# Logic_Analyzer.net
KiCad netlist of a schematic drawn in Altium Designer
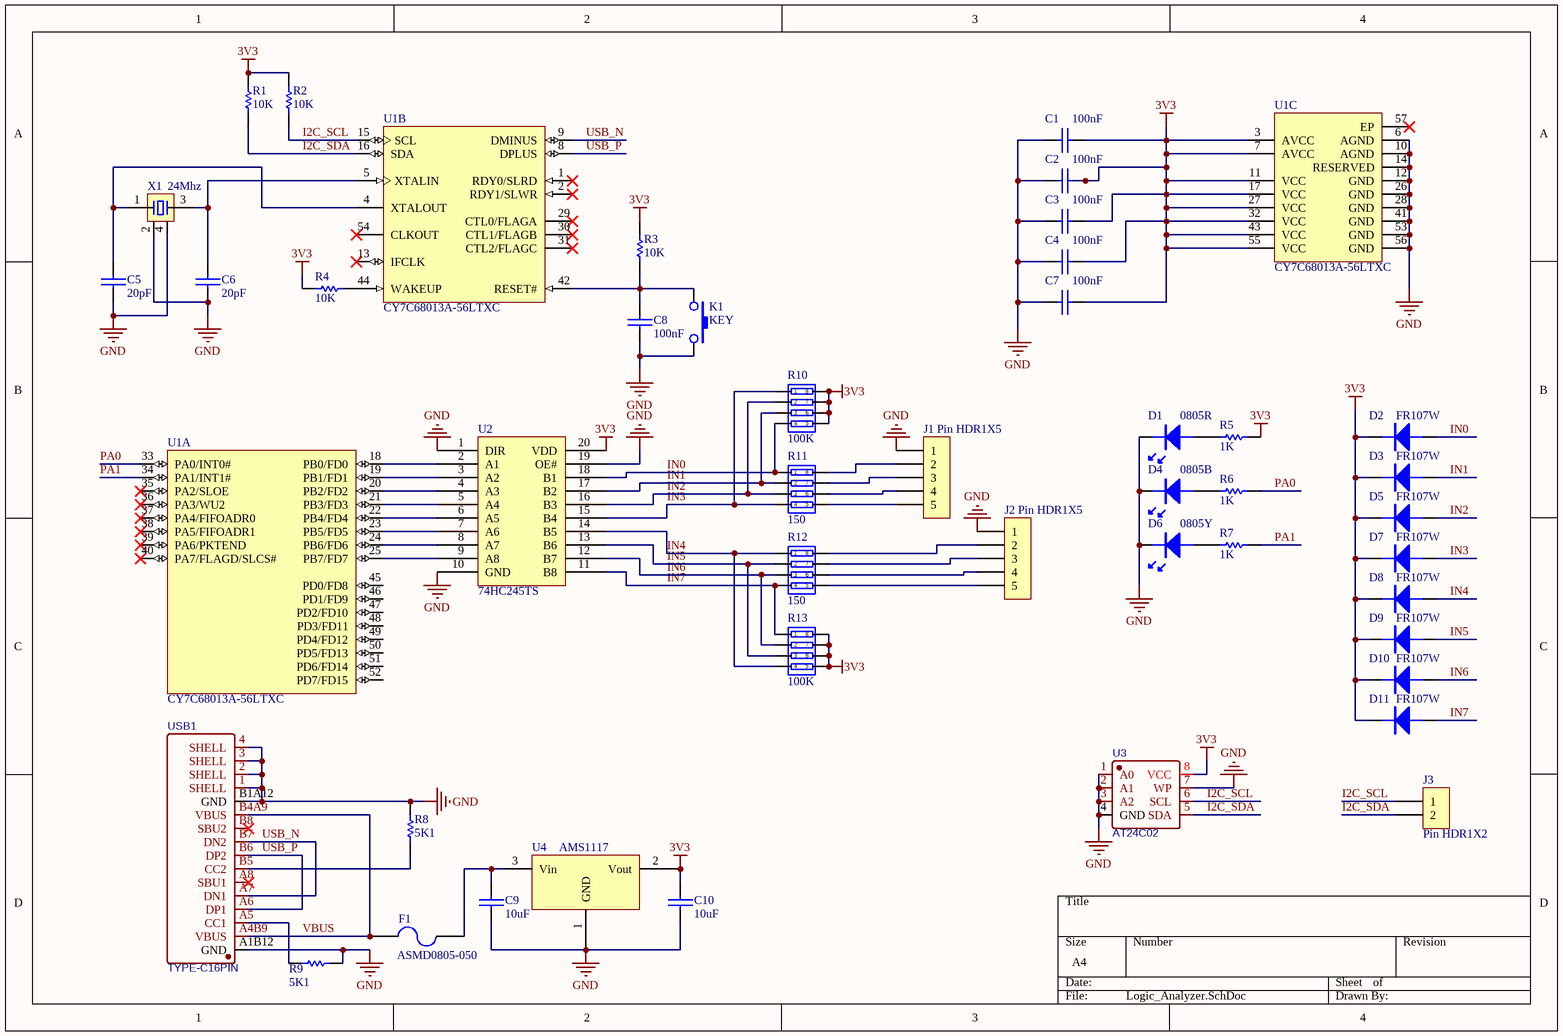
[diagram p0: Logic_Analyzer.SchDoc]

(export (version "E")
  (design (tool "Eeschema 10.0.6"))
  (components
    (comp (ref "C1")
      (value "100nF")
      (footprint "0603C")
      (description "无极性电容")
      (libsource (lib "电容") (part "CAP"))
    )
    (comp (ref "C2")
      (value "100nF")
      (footprint "0603C")
      (description "无极性电容")
      (libsource (lib "电容") (part "CAP"))
    )
    (comp (ref "C3")
      (value "100nF")
      (footprint "0603C")
      (description "无极性电容")
      (libsource (lib "电容") (part "CAP"))
    )
    (comp (ref "C4")
      (value "100nF")
      (footprint "0603C")
      (description "无极性电容")
      (libsource (lib "电容") (part "CAP"))
    )
    (comp (ref "C5")
      (value "20pF")
      (footprint "0603C")
      (description "无极性电容")
      (libsource (lib "电容") (part "CAP"))
    )
    (comp (ref "C6")
      (value "20pF")
      (footprint "0603C")
      (description "无极性电容")
      (libsource (lib "电容") (part "CAP"))
    )
    (comp (ref "C7")
      (value "100nF")
      (footprint "0603C")
      (description "无极性电容")
      (libsource (lib "电容") (part "CAP"))
    )
    (comp (ref "C8")
      (value "100nF")
      (footprint "0603C")
      (description "无极性电容")
      (libsource (lib "电容") (part "CAP"))
    )
    (comp (ref "C9")
      (value "10uF")
      (footprint "0603C")
      (description "无极性电容")
      (libsource (lib "电容") (part "CAP"))
    )
    (comp (ref "C10")
      (value "10uF")
      (footprint "0603C")
      (description "无极性电容")
      (libsource (lib "电容") (part "CAP"))
    )
    (comp (ref "D1") (value "0805R") (footprint "LED-0805R") (libsource (lib "LED") (part "LED")))
    (comp (ref "D2")
      (value "FR107W")
      (footprint "SOD-123")
      (description "普通二极管")
      (libsource (lib "二极管") (part "DIODE"))
    )
    (comp (ref "D3")
      (value "FR107W")
      (footprint "SOD-123")
      (description "普通二极管")
      (libsource (lib "二极管") (part "DIODE"))
    )
    (comp (ref "D4") (value "0805B") (footprint "LED-0805B") (libsource (lib "LED") (part "LED")))
    (comp (ref "D5")
      (value "FR107W")
      (footprint "SOD-123")
      (description "普通二极管")
      (libsource (lib "二极管") (part "DIODE"))
    )
    (comp (ref "D6") (value "0805Y") (footprint "LED-0805Y") (libsource (lib "LED") (part "LED")))
    (comp (ref "D7")
      (value "FR107W")
      (footprint "SOD-123")
      (description "普通二极管")
      (libsource (lib "二极管") (part "DIODE"))
    )
    (comp (ref "D8")
      (value "FR107W")
      (footprint "SOD-123")
      (description "普通二极管")
      (libsource (lib "二极管") (part "DIODE"))
    )
    (comp (ref "D9")
      (value "FR107W")
      (footprint "SOD-123")
      (description "普通二极管")
      (libsource (lib "二极管") (part "DIODE"))
    )
    (comp (ref "D10")
      (value "FR107W")
      (footprint "SOD-123")
      (description "普通二极管")
      (libsource (lib "二极管") (part "DIODE"))
    )
    (comp (ref "D11")
      (value "FR107W")
      (footprint "SOD-123")
      (description "普通二极管")
      (libsource (lib "二极管") (part "DIODE"))
    )
    (comp (ref "F1") (value "ASMD0805-050") (footprint "FUSE-0805") (libsource (lib "保险丝") (part "FUSE")))
    (comp (ref "J1")
      (value "Pin HDR1X5")
      (footprint "Pin HDR1X5/2.54mm-S-SMD")
      (libsource (lib "排针") (part "Pin HDR1X5"))
    )
    (comp (ref "J2")
      (value "Pin HDR1X5")
      (footprint "Pin HDR1X5/2.54mm-S-SMD")
      (libsource (lib "排针") (part "Pin HDR1X5"))
    )
    (comp (ref "J3")
      (value "Pin HDR1X2")
      (footprint "Pin HDR1X2/2.54mm-S")
      (libsource (lib "排针") (part "Pin HDR1X2"))
    )
    (comp (ref "K1")
      (value "KEY")
      (footprint "SW-SMD_L4.0-W2.9-P4.15-EH")
      (libsource (lib "轻触开关") (part "KEY"))
    )
    (comp (ref "R1") (value "10K") (footprint "0603R") (libsource (lib "电阻") (part "RES")))
    (comp (ref "R2") (value "10K") (footprint "0603R") (libsource (lib "电阻") (part "RES")))
    (comp (ref "R3") (value "10K") (footprint "0603R") (libsource (lib "电阻") (part "RES")))
    (comp (ref "R4") (value "10K") (footprint "0603R") (libsource (lib "电阻") (part "RES")))
    (comp (ref "R5") (value "1K") (footprint "0603R") (libsource (lib "电阻") (part "RES")))
    (comp (ref "R6") (value "1K") (footprint "0603R") (libsource (lib "电阻") (part "RES")))
    (comp (ref "R7") (value "1K") (footprint "0603R") (libsource (lib "电阻") (part "RES")))
    (comp (ref "R8") (value "5K1") (footprint "0603R") (libsource (lib "电阻") (part "RES")))
    (comp (ref "R9") (value "5K1") (footprint "0603R") (libsource (lib "电阻") (part "RES")))
    (comp (ref "R10")
      (value "100K")
      (footprint "RES-ARRAY-SMD_0603-8P-L3.2-W1.6-BL")
      (description "网络排阻4R")
      (libsource (lib "电阻") (part "RES_ARRAY*4"))
    )
    (comp (ref "R11")
      (value "150")
      (footprint "RES-ARRAY-SMD_0603-8P-L3.2-W1.6-BL")
      (description "网络排阻4R")
      (libsource (lib "电阻") (part "RES_ARRAY*4"))
    )
    (comp (ref "R12")
      (value "150")
      (footprint "RES-ARRAY-SMD_0603-8P-L3.2-W1.6-BL")
      (description "网络排阻4R")
      (libsource (lib "电阻") (part "RES_ARRAY*4"))
    )
    (comp (ref "R13")
      (value "100K")
      (footprint "RES-ARRAY-SMD_0603-8P-L3.2-W1.6-BL")
      (description "网络排阻4R")
      (libsource (lib "电阻") (part "RES_ARRAY*4"))
    )
    (comp (ref "U1")
      (value "CY7C68013A-56LTXC")
      (footprint "CYP-LTX56-5200X4500TP_M")
      (fields (field (name "MANUFACTURER") "Cypress"))
      (libsource (lib "Cypress USB Controllers") (part "CY7C68013A-56LTXC"))
    )
    (comp (ref "U2") (value "74HC245TS") (footprint "TSSOP20") (libsource (lib "74系列芯片") (part "74HC245TS")))
    (comp (ref "U3")
      (value "AT24C02")
      (footprint "SOP8")
      (fields (field (name "BOM_SUPPLIER PART") "C688857") (field (name "CONTRIBUTOR") "LCSC"))
      (libsource (lib "未分类IC") (part "AT24C02"))
    )
    (comp (ref "U4")
      (value "AMS1117")
      (footprint "SOT223")
      (description "三端稳压芯片")
      (libsource (lib "电源芯片") (part "AMS1117"))
    )
    (comp (ref "USB1")
      (value "TYPE-C16PIN")
      (footprint "USB-C-SMD_TYPE-C16PIN")
      (fields (field (name "BOM_SUPPLIER PART") "C393939") (field (name "CONTRIBUTOR") "LCSC"))
      (libsource (lib "USB") (part "USB-C_16PIN"))
    )
    (comp (ref "X1")
      (value "24Mhz")
      (footprint "OSC 3225-4P")
      (description "4脚无源晶振")
      (libsource (lib "晶振") (part "XTAL-4P"))
    )
  )
  (nets
    (net (code "1") (name "/I2C_SCL") (class "Default")
      (node (ref "J3") (pin "1") (pinfunction "1_1") (pintype "passive"))
      (node (ref "R2") (pin "1") (pinfunction "1_1") (pintype "passive"))
      (node (ref "U1") (pin "15") (pinfunction "SCL_15") (pintype "bidirectional"))
      (node (ref "U3") (pin "6") (pinfunction "SCL_6") (pintype "passive"))
    )
    (net (code "2") (name "/I2C_SDA") (class "Default")
      (node (ref "J3") (pin "2") (pinfunction "2_2") (pintype "passive"))
      (node (ref "R1") (pin "1") (pinfunction "1_1") (pintype "passive"))
      (node (ref "U1") (pin "16") (pinfunction "SDA_16") (pintype "bidirectional"))
      (node (ref "U3") (pin "5") (pinfunction "SDA_5") (pintype "passive"))
    )
    (net (code "3") (name "/IN0") (class "Default")
      (node (ref "D2") (pin "A") (pinfunction "A_A") (pintype "passive"))
      (node (ref "R10") (pin "4") (pinfunction "4_4") (pintype "passive"))
      (node (ref "R11") (pin "1") (pinfunction "1_1") (pintype "passive"))
      (node (ref "U2") (pin "18") (pinfunction "B1_18") (pintype "passive"))
    )
    (net (code "4") (name "/IN1") (class "Default")
      (node (ref "D3") (pin "A") (pinfunction "A_A") (pintype "passive"))
      (node (ref "R10") (pin "3") (pinfunction "3_3") (pintype "passive"))
      (node (ref "R11") (pin "2") (pinfunction "2_2") (pintype "passive"))
      (node (ref "U2") (pin "17") (pinfunction "B2_17") (pintype "passive"))
    )
    (net (code "5") (name "/IN2") (class "Default")
      (node (ref "D5") (pin "A") (pinfunction "A_A") (pintype "passive"))
      (node (ref "R10") (pin "2") (pinfunction "2_2") (pintype "passive"))
      (node (ref "R11") (pin "3") (pinfunction "3_3") (pintype "passive"))
      (node (ref "U2") (pin "16") (pinfunction "B3_16") (pintype "passive"))
    )
    (net (code "6") (name "/IN3") (class "Default")
      (node (ref "D7") (pin "A") (pinfunction "A_A") (pintype "passive"))
      (node (ref "R10") (pin "1") (pinfunction "1_1") (pintype "passive"))
      (node (ref "R11") (pin "4") (pinfunction "4_4") (pintype "passive"))
      (node (ref "U2") (pin "15") (pinfunction "B4_15") (pintype "passive"))
    )
    (net (code "7") (name "/IN4") (class "Default")
      (node (ref "D8") (pin "A") (pinfunction "A_A") (pintype "passive"))
      (node (ref "R12") (pin "1") (pinfunction "1_1") (pintype "passive"))
      (node (ref "R13") (pin "4") (pinfunction "4_4") (pintype "passive"))
      (node (ref "U2") (pin "14") (pinfunction "B5_14") (pintype "passive"))
    )
    (net (code "8") (name "/IN5") (class "Default")
      (node (ref "D9") (pin "A") (pinfunction "A_A") (pintype "passive"))
      (node (ref "R12") (pin "2") (pinfunction "2_2") (pintype "passive"))
      (node (ref "R13") (pin "3") (pinfunction "3_3") (pintype "passive"))
      (node (ref "U2") (pin "13") (pinfunction "B6_13") (pintype "passive"))
    )
    (net (code "9") (name "/IN6") (class "Default")
      (node (ref "D10") (pin "A") (pinfunction "A_A") (pintype "passive"))
      (node (ref "R12") (pin "3") (pinfunction "3_3") (pintype "passive"))
      (node (ref "R13") (pin "2") (pinfunction "2_2") (pintype "passive"))
      (node (ref "U2") (pin "12") (pinfunction "B7_12") (pintype "passive"))
    )
    (net (code "10") (name "/IN7") (class "Default")
      (node (ref "D11") (pin "A") (pinfunction "A_A") (pintype "passive"))
      (node (ref "R12") (pin "4") (pinfunction "4_4") (pintype "passive"))
      (node (ref "R13") (pin "1") (pinfunction "1_1") (pintype "passive"))
      (node (ref "U2") (pin "11") (pinfunction "B8_11") (pintype "passive"))
    )
    (net (code "11") (name "/PA0") (class "Default")
      (node (ref "R6") (pin "1") (pinfunction "1_1") (pintype "passive"))
      (node (ref "U1") (pin "33") (pinfunction "PA0/INT0#_33") (pintype "bidirectional"))
    )
    (net (code "12") (name "/PA1") (class "Default")
      (node (ref "R7") (pin "1") (pinfunction "1_1") (pintype "passive"))
      (node (ref "U1") (pin "34") (pinfunction "PA1/INT1#_34") (pintype "bidirectional"))
    )
    (net (code "13") (name "/USB_N") (class "Default")
      (node (ref "U1") (pin "9") (pinfunction "DMINUS_9") (pintype "bidirectional"))
      (node (ref "USB1") (pin "A7") (pinfunction "DN1_A7") (pintype "passive"))
      (node (ref "USB1") (pin "B7") (pinfunction "DN2_B7") (pintype "passive"))
    )
    (net (code "14") (name "/USB_P") (class "Default")
      (node (ref "U1") (pin "8") (pinfunction "DPLUS_8") (pintype "bidirectional"))
      (node (ref "USB1") (pin "A6") (pinfunction "DP1_A6") (pintype "passive"))
      (node (ref "USB1") (pin "B6") (pinfunction "DP2_B6") (pintype "passive"))
    )
    (net (code "15") (name "/VBUS") (class "Default")
      (node (ref "F1") (pin "1") (pinfunction "1_1") (pintype "passive"))
      (node (ref "USB1") (pin "A4B9") (pinfunction "VBUS_A4B9") (pintype "passive"))
      (node (ref "USB1") (pin "B4A9") (pinfunction "VBUS_B4A9") (pintype "passive"))
    )
    (net (code "16") (name "3V3") (class "Default")
      (node (ref "C1") (pin "1") (pinfunction "1_1") (pintype "passive"))
      (node (ref "C10") (pin "2") (pinfunction "2_2") (pintype "passive"))
      (node (ref "C2") (pin "1") (pinfunction "1_1") (pintype "passive"))
      (node (ref "C3") (pin "1") (pinfunction "1_1") (pintype "passive"))
      (node (ref "C4") (pin "1") (pinfunction "1_1") (pintype "passive"))
      (node (ref "C7") (pin "1") (pinfunction "1_1") (pintype "passive"))
      (node (ref "D10") (pin "K") (pinfunction "K_K") (pintype "passive"))
      (node (ref "D11") (pin "K") (pinfunction "K_K") (pintype "passive"))
      (node (ref "D2") (pin "K") (pinfunction "K_K") (pintype "passive"))
      (node (ref "D3") (pin "K") (pinfunction "K_K") (pintype "passive"))
      (node (ref "D5") (pin "K") (pinfunction "K_K") (pintype "passive"))
      (node (ref "D7") (pin "K") (pinfunction "K_K") (pintype "passive"))
      (node (ref "D8") (pin "K") (pinfunction "K_K") (pintype "passive"))
      (node (ref "D9") (pin "K") (pinfunction "K_K") (pintype "passive"))
      (node (ref "R1") (pin "2") (pinfunction "2_2") (pintype "passive"))
      (node (ref "R10") (pin "5") (pinfunction "5_5") (pintype "passive"))
      (node (ref "R10") (pin "6") (pinfunction "6_6") (pintype "passive"))
      (node (ref "R10") (pin "7") (pinfunction "7_7") (pintype "passive"))
      (node (ref "R10") (pin "8") (pinfunction "8_8") (pintype "passive"))
      (node (ref "R13") (pin "5") (pinfunction "5_5") (pintype "passive"))
      (node (ref "R13") (pin "6") (pinfunction "6_6") (pintype "passive"))
      (node (ref "R13") (pin "7") (pinfunction "7_7") (pintype "passive"))
      (node (ref "R13") (pin "8") (pinfunction "8_8") (pintype "passive"))
      (node (ref "R2") (pin "2") (pinfunction "2_2") (pintype "passive"))
      (node (ref "R3") (pin "2") (pinfunction "2_2") (pintype "passive"))
      (node (ref "R4") (pin "2") (pinfunction "2_2") (pintype "passive"))
      (node (ref "R5") (pin "1") (pinfunction "1_1") (pintype "passive"))
      (node (ref "U1") (pin "11") (pinfunction "VCC_11") (pintype "power_in"))
      (node (ref "U1") (pin "17") (pinfunction "VCC_17") (pintype "power_in"))
      (node (ref "U1") (pin "27") (pinfunction "VCC_27") (pintype "power_in"))
      (node (ref "U1") (pin "3") (pinfunction "AVCC_3") (pintype "power_in"))
      (node (ref "U1") (pin "32") (pinfunction "VCC_32") (pintype "power_in"))
      (node (ref "U1") (pin "43") (pinfunction "VCC_43") (pintype "power_in"))
      (node (ref "U1") (pin "55") (pinfunction "VCC_55") (pintype "power_in"))
      (node (ref "U1") (pin "7") (pinfunction "AVCC_7") (pintype "power_in"))
      (node (ref "U2") (pin "20") (pinfunction "VDD_20") (pintype "passive"))
      (node (ref "U3") (pin "8") (pinfunction "VCC_8") (pintype "passive"))
      (node (ref "U4") (pin "2") (pinfunction "Vout_2") (pintype "passive"))
    )
    (net (code "17") (name "GND") (class "Default")
      (node (ref "C1") (pin "2") (pinfunction "2_2") (pintype "passive"))
      (node (ref "C10") (pin "1") (pinfunction "1_1") (pintype "passive"))
      (node (ref "C2") (pin "2") (pinfunction "2_2") (pintype "passive"))
      (node (ref "C3") (pin "2") (pinfunction "2_2") (pintype "passive"))
      (node (ref "C4") (pin "2") (pinfunction "2_2") (pintype "passive"))
      (node (ref "C5") (pin "1") (pinfunction "1_1") (pintype "passive"))
      (node (ref "C6") (pin "1") (pinfunction "1_1") (pintype "passive"))
      (node (ref "C7") (pin "2") (pinfunction "2_2") (pintype "passive"))
      (node (ref "C8") (pin "1") (pinfunction "1_1") (pintype "passive"))
      (node (ref "C9") (pin "1") (pinfunction "1_1") (pintype "passive"))
      (node (ref "D1") (pin "K") (pinfunction "K_K") (pintype "passive"))
      (node (ref "D4") (pin "K") (pinfunction "K_K") (pintype "passive"))
      (node (ref "D6") (pin "K") (pinfunction "K_K") (pintype "passive"))
      (node (ref "J1") (pin "1") (pinfunction "1_1") (pintype "passive"))
      (node (ref "J2") (pin "1") (pinfunction "1_1") (pintype "passive"))
      (node (ref "K1") (pin "3") (pinfunction "3_3") (pintype "passive"))
      (node (ref "R8") (pin "1") (pinfunction "1_1") (pintype "passive"))
      (node (ref "R9") (pin "1") (pinfunction "1_1") (pintype "passive"))
      (node (ref "U1") (pin "10") (pinfunction "AGND_10") (pintype "power_in"))
      (node (ref "U1") (pin "12") (pinfunction "GND_12") (pintype "power_in"))
      (node (ref "U1") (pin "14") (pinfunction "RESERVED_14") (pintype "power_in"))
      (node (ref "U1") (pin "26") (pinfunction "GND_26") (pintype "power_in"))
      (node (ref "U1") (pin "28") (pinfunction "GND_28") (pintype "power_in"))
      (node (ref "U1") (pin "41") (pinfunction "GND_41") (pintype "power_in"))
      (node (ref "U1") (pin "53") (pinfunction "GND_53") (pintype "power_in"))
      (node (ref "U1") (pin "56") (pinfunction "GND_56") (pintype "power_in"))
      (node (ref "U1") (pin "6") (pinfunction "AGND_6") (pintype "power_in"))
      (node (ref "U2") (pin "1") (pinfunction "DIR_1") (pintype "passive"))
      (node (ref "U2") (pin "10") (pinfunction "GND_10") (pintype "passive"))
      (node (ref "U2") (pin "19") (pinfunction "OE#_19") (pintype "passive"))
      (node (ref "U3") (pin "1") (pinfunction "A0_1") (pintype "passive"))
      (node (ref "U3") (pin "2") (pinfunction "A1_2") (pintype "passive"))
      (node (ref "U3") (pin "3") (pinfunction "A2_3") (pintype "passive"))
      (node (ref "U3") (pin "4") (pinfunction "GND_4") (pintype "passive"))
      (node (ref "U3") (pin "7") (pinfunction "WP_7") (pintype "passive"))
      (node (ref "U4") (pin "1") (pinfunction "GND_1") (pintype "passive"))
      (node (ref "USB1") (pin "1") (pinfunction "SHELL_1") (pintype "passive"))
      (node (ref "USB1") (pin "2") (pinfunction "SHELL_2") (pintype "passive"))
      (node (ref "USB1") (pin "3") (pinfunction "SHELL_3") (pintype "passive"))
      (node (ref "USB1") (pin "4") (pinfunction "SHELL_4") (pintype "passive"))
      (node (ref "USB1") (pin "A1B12") (pinfunction "GND_A1B12") (pintype "passive"))
      (node (ref "USB1") (pin "B1A12") (pinfunction "GND_B1A12") (pintype "passive"))
      (node (ref "X1") (pin "2") (pinfunction "2_2") (pintype "passive"))
      (node (ref "X1") (pin "4") (pinfunction "4_4") (pintype "passive"))
    )
    (net (code "18") (name "Net-(D1-PadA)") (class "Default")
      (node (ref "D1") (pin "A") (pinfunction "A_A") (pintype "passive"))
      (node (ref "R5") (pin "2") (pinfunction "2_2") (pintype "passive"))
    )
    (net (code "19") (name "Net-(D4-PadA)") (class "Default")
      (node (ref "D4") (pin "A") (pinfunction "A_A") (pintype "passive"))
      (node (ref "R6") (pin "2") (pinfunction "2_2") (pintype "passive"))
    )
    (net (code "20") (name "Net-(D6-PadA)") (class "Default")
      (node (ref "D6") (pin "A") (pinfunction "A_A") (pintype "passive"))
      (node (ref "R7") (pin "2") (pinfunction "2_2") (pintype "passive"))
    )
    (net (code "21") (name "Net-(J1-Pad2)") (class "Default")
      (node (ref "J1") (pin "2") (pinfunction "2_2") (pintype "passive"))
      (node (ref "R11") (pin "8") (pinfunction "8_8") (pintype "passive"))
    )
    (net (code "22") (name "Net-(J1-Pad3)") (class "Default")
      (node (ref "J1") (pin "3") (pinfunction "3_3") (pintype "passive"))
      (node (ref "R11") (pin "7") (pinfunction "7_7") (pintype "passive"))
    )
    (net (code "23") (name "Net-(J1-Pad4)") (class "Default")
      (node (ref "J1") (pin "4") (pinfunction "4_4") (pintype "passive"))
      (node (ref "R11") (pin "6") (pinfunction "6_6") (pintype "passive"))
    )
    (net (code "24") (name "Net-(J1-Pad5)") (class "Default")
      (node (ref "J1") (pin "5") (pinfunction "5_5") (pintype "passive"))
      (node (ref "R11") (pin "5") (pinfunction "5_5") (pintype "passive"))
    )
    (net (code "25") (name "Net-(J2-Pad2)") (class "Default")
      (node (ref "J2") (pin "2") (pinfunction "2_2") (pintype "passive"))
      (node (ref "R12") (pin "8") (pinfunction "8_8") (pintype "passive"))
    )
    (net (code "26") (name "Net-(J2-Pad3)") (class "Default")
      (node (ref "J2") (pin "3") (pinfunction "3_3") (pintype "passive"))
      (node (ref "R12") (pin "7") (pinfunction "7_7") (pintype "passive"))
    )
    (net (code "27") (name "Net-(J2-Pad4)") (class "Default")
      (node (ref "J2") (pin "4") (pinfunction "4_4") (pintype "passive"))
      (node (ref "R12") (pin "6") (pinfunction "6_6") (pintype "passive"))
    )
    (net (code "28") (name "Net-(J2-Pad5)") (class "Default")
      (node (ref "J2") (pin "5") (pinfunction "5_5") (pintype "passive"))
      (node (ref "R12") (pin "5") (pinfunction "5_5") (pintype "passive"))
    )
    (net (code "29") (name "Net-(U1A-PB0{slash}FD0)") (class "Default")
      (node (ref "U1") (pin "18") (pinfunction "PB0/FD0_18") (pintype "bidirectional"))
      (node (ref "U2") (pin "2") (pinfunction "A1_2") (pintype "passive"))
    )
    (net (code "30") (name "Net-(U1A-PB1{slash}FD1)") (class "Default")
      (node (ref "U1") (pin "19") (pinfunction "PB1/FD1_19") (pintype "bidirectional"))
      (node (ref "U2") (pin "3") (pinfunction "A2_3") (pintype "passive"))
    )
    (net (code "31") (name "Net-(U1A-PB2{slash}FD2)") (class "Default")
      (node (ref "U1") (pin "20") (pinfunction "PB2/FD2_20") (pintype "bidirectional"))
      (node (ref "U2") (pin "4") (pinfunction "A3_4") (pintype "passive"))
    )
    (net (code "32") (name "Net-(U1A-PB3{slash}FD3)") (class "Default")
      (node (ref "U1") (pin "21") (pinfunction "PB3/FD3_21") (pintype "bidirectional"))
      (node (ref "U2") (pin "5") (pinfunction "A4_5") (pintype "passive"))
    )
    (net (code "33") (name "Net-(U1A-PB4{slash}FD4)") (class "Default")
      (node (ref "U1") (pin "22") (pinfunction "PB4/FD4_22") (pintype "bidirectional"))
      (node (ref "U2") (pin "6") (pinfunction "A5_6") (pintype "passive"))
    )
    (net (code "34") (name "Net-(U1A-PB5{slash}FD5)") (class "Default")
      (node (ref "U1") (pin "23") (pinfunction "PB5/FD5_23") (pintype "bidirectional"))
      (node (ref "U2") (pin "7") (pinfunction "A6_7") (pintype "passive"))
    )
    (net (code "35") (name "Net-(U1A-PB6{slash}FD6)") (class "Default")
      (node (ref "U1") (pin "24") (pinfunction "PB6/FD6_24") (pintype "bidirectional"))
      (node (ref "U2") (pin "8") (pinfunction "A7_8") (pintype "passive"))
    )
    (net (code "36") (name "Net-(U1A-PB7{slash}FD7)") (class "Default")
      (node (ref "U1") (pin "25") (pinfunction "PB7/FD7_25") (pintype "bidirectional"))
      (node (ref "U2") (pin "9") (pinfunction "A8_9") (pintype "passive"))
    )
    (net (code "37") (name "Net-(U1B-RESET#)") (class "Default")
      (node (ref "C8") (pin "2") (pinfunction "2_2") (pintype "passive"))
      (node (ref "K1") (pin "1") (pinfunction "1_1") (pintype "passive"))
      (node (ref "R3") (pin "1") (pinfunction "1_1") (pintype "passive"))
      (node (ref "U1") (pin "42") (pinfunction "RESET#_42") (pintype "input"))
    )
    (net (code "38") (name "Net-(U1B-WAKEUP)") (class "Default")
      (node (ref "R4") (pin "1") (pinfunction "1_1") (pintype "passive"))
      (node (ref "U1") (pin "44") (pinfunction "WAKEUP_44") (pintype "input"))
    )
    (net (code "39") (name "Net-(U1B-XTALIN)") (class "Default")
      (node (ref "C6") (pin "2") (pinfunction "2_2") (pintype "passive"))
      (node (ref "U1") (pin "5") (pinfunction "XTALIN_5") (pintype "input"))
      (node (ref "X1") (pin "3") (pinfunction "3_3") (pintype "passive"))
    )
    (net (code "40") (name "Net-(U1B-XTALOUT)") (class "Default")
      (node (ref "C5") (pin "2") (pinfunction "2_2") (pintype "passive"))
      (node (ref "U1") (pin "4") (pinfunction "XTALOUT_4") (pintype "passive"))
      (node (ref "X1") (pin "1") (pinfunction "1_1") (pintype "passive"))
    )
    (net (code "41") (name "Net-(U4-Vin)") (class "Default")
      (node (ref "C9") (pin "2") (pinfunction "2_2") (pintype "passive"))
      (node (ref "F1") (pin "2") (pinfunction "2_2") (pintype "passive"))
      (node (ref "U4") (pin "3") (pinfunction "Vin_3") (pintype "passive"))
    )
    (net (code "42") (name "Net-(USB1-CC1)") (class "Default")
      (node (ref "R9") (pin "2") (pinfunction "2_2") (pintype "passive"))
      (node (ref "USB1") (pin "A5") (pinfunction "CC1_A5") (pintype "passive"))
    )
    (net (code "43") (name "Net-(USB1-CC2)") (class "Default")
      (node (ref "R8") (pin "2") (pinfunction "2_2") (pintype "passive"))
      (node (ref "USB1") (pin "B5") (pinfunction "CC2_B5") (pintype "passive"))
    )
    (net (code "44") (name "unconnected-(U1A-PA2{slash}SLOE-Pad35)") (class "Default")
      (node (ref "U1") (pin "35") (pinfunction "PA2/SLOE_35") (pintype "bidirectional+no_connect"))
    )
    (net (code "45") (name "unconnected-(U1A-PA3{slash}WU2-Pad36)") (class "Default")
      (node (ref "U1") (pin "36") (pinfunction "PA3/WU2_36") (pintype "bidirectional+no_connect"))
    )
    (net (code "46") (name "unconnected-(U1A-PA4{slash}FIFOADR0-Pad37)") (class "Default")
      (node (ref "U1") (pin "37") (pinfunction "PA4/FIFOADR0_37") (pintype "bidirectional+no_connect"))
    )
    (net (code "47") (name "unconnected-(U1A-PA5{slash}FIFOADR1-Pad38)") (class "Default")
      (node (ref "U1") (pin "38") (pinfunction "PA5/FIFOADR1_38") (pintype "bidirectional+no_connect"))
    )
    (net (code "48") (name "unconnected-(U1A-PA6{slash}PKTEND-Pad39)") (class "Default")
      (node (ref "U1") (pin "39") (pinfunction "PA6/PKTEND_39") (pintype "bidirectional+no_connect"))
    )
    (net (code "49") (name "unconnected-(U1A-PA7{slash}FLAGD{slash}SLCS#-Pad40)") (class "Default")
      (node (ref "U1") (pin "40") (pinfunction "PA7/FLAGD/SLCS#_40") (pintype "bidirectional+no_connect"))
    )
    (net (code "50") (name "unconnected-(U1A-PD0{slash}FD8-Pad45)") (class "Default")
      (node (ref "U1") (pin "45") (pinfunction "PD0/FD8_45") (pintype "bidirectional"))
    )
    (net (code "51") (name "unconnected-(U1A-PD1{slash}FD9-Pad46)") (class "Default")
      (node (ref "U1") (pin "46") (pinfunction "PD1/FD9_46") (pintype "bidirectional"))
    )
    (net (code "52") (name "unconnected-(U1A-PD2{slash}FD10-Pad47)") (class "Default")
      (node (ref "U1") (pin "47") (pinfunction "PD2/FD10_47") (pintype "bidirectional"))
    )
    (net (code "53") (name "unconnected-(U1A-PD3{slash}FD11-Pad48)") (class "Default")
      (node (ref "U1") (pin "48") (pinfunction "PD3/FD11_48") (pintype "bidirectional"))
    )
    (net (code "54") (name "unconnected-(U1A-PD4{slash}FD12-Pad49)") (class "Default")
      (node (ref "U1") (pin "49") (pinfunction "PD4/FD12_49") (pintype "bidirectional"))
    )
    (net (code "55") (name "unconnected-(U1A-PD5{slash}FD13-Pad50)") (class "Default")
      (node (ref "U1") (pin "50") (pinfunction "PD5/FD13_50") (pintype "bidirectional"))
    )
    (net (code "56") (name "unconnected-(U1A-PD6{slash}FD14-Pad51)") (class "Default")
      (node (ref "U1") (pin "51") (pinfunction "PD6/FD14_51") (pintype "bidirectional"))
    )
    (net (code "57") (name "unconnected-(U1A-PD7{slash}FD15-Pad52)") (class "Default")
      (node (ref "U1") (pin "52") (pinfunction "PD7/FD15_52") (pintype "bidirectional"))
    )
    (net (code "58") (name "unconnected-(U1B-CLKOUT-Pad54)") (class "Default")
      (node (ref "U1") (pin "54") (pinfunction "CLKOUT_54") (pintype "tri_state+no_connect"))
    )
    (net (code "59") (name "unconnected-(U1B-CTL0{slash}FLAGA-Pad29)") (class "Default")
      (node (ref "U1") (pin "29") (pinfunction "CTL0/FLAGA_29") (pintype "tri_state+no_connect"))
    )
    (net (code "60") (name "unconnected-(U1B-CTL1{slash}FLAGB-Pad30)") (class "Default")
      (node (ref "U1") (pin "30") (pinfunction "CTL1/FLAGB_30") (pintype "tri_state+no_connect"))
    )
    (net (code "61") (name "unconnected-(U1B-CTL2{slash}FLAGC-Pad31)") (class "Default")
      (node (ref "U1") (pin "31") (pinfunction "CTL2/FLAGC_31") (pintype "tri_state+no_connect"))
    )
    (net (code "62") (name "unconnected-(U1B-IFCLK-Pad13)") (class "Default")
      (node (ref "U1") (pin "13") (pinfunction "IFCLK_13") (pintype "bidirectional+no_connect"))
    )
    (net (code "63") (name "unconnected-(U1B-RDY0{slash}SLRD-Pad1)") (class "Default")
      (node (ref "U1") (pin "1") (pinfunction "RDY0/SLRD_1") (pintype "input+no_connect"))
    )
    (net (code "64") (name "unconnected-(U1B-RDY1{slash}SLWR-Pad2)") (class "Default")
      (node (ref "U1") (pin "2") (pinfunction "RDY1/SLWR_2") (pintype "input+no_connect"))
    )
    (net (code "65") (name "unconnected-(U1C-EP-Pad57)") (class "Default")
      (node (ref "U1") (pin "57") (pinfunction "EP_57") (pintype "passive+no_connect"))
    )
    (net (code "66") (name "unconnected-(USB1-SBU1-PadA8)") (class "Default")
      (node (ref "USB1") (pin "A8") (pinfunction "SBU1_A8") (pintype "passive+no_connect"))
    )
    (net (code "67") (name "unconnected-(USB1-SBU2-PadB8)") (class "Default")
      (node (ref "USB1") (pin "B8") (pinfunction "SBU2_B8") (pintype "passive+no_connect"))
    )
  )
)
